# BHI_EVAL.net
KiCad netlist of a schematic drawn in Altium Designer
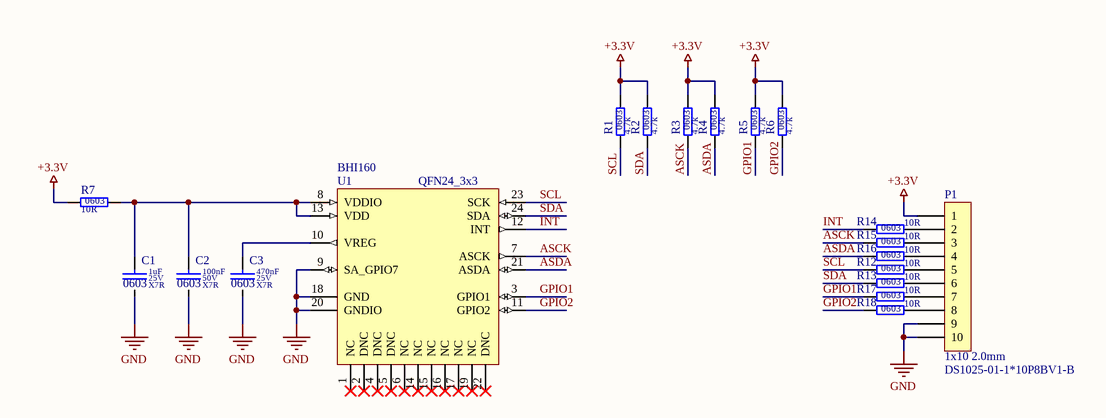
[diagram p0: BHI_EVAL.SchDoc]

(export (version "E")
  (design (tool "Eeschema 10.0.6"))
  (components
    (comp (ref "C1")
      (value "1uF")
      (footprint "C_0603_1608")
      (description "Capacitor")
      (fields
        (field (name "DIELECTRIC") "X7R")
        (field (name "VOLTAGE") "25V")
        (field (name "SCH_FOOTPRINT") "0603")
        (field (name "PART NUMBER") "C_1uF_25V_X7R_0603_10")
        (field (name "MANUFACTURER") "Samsung")
      )
      (libsource (lib "Library") (part "C"))
    )
    (comp (ref "C2")
      (value "100nF")
      (footprint "C_0603_1608")
      (description "Capacitor")
      (fields
        (field (name "DIELECTRIC") "X7R")
        (field (name "VOLTAGE") "50V")
        (field (name "SCH_FOOTPRINT") "0603")
        (field (name "PART NUMBER") "C_100nF_50V_X7R_0603_5")
        (field (name "MANUFACTURER") "Samsung")
      )
      (libsource (lib "Library") (part "C"))
    )
    (comp (ref "C3")
      (value "470nF")
      (footprint "C_0603_1608")
      (description "Capacitor")
      (fields
        (field (name "DIELECTRIC") "X7R")
        (field (name "VOLTAGE") "25V")
        (field (name "SCH_FOOTPRINT") "0603")
        (field (name "PART NUMBER") "C_470nF_25V_X7R_0603_10")
        (field (name "MANUFACTURER") "Murata")
      )
      (libsource (lib "Library") (part "C"))
    )
    (comp (ref "P1")
      (value "DS1025-01-1*10P8BV1-B")
      (footprint "P_HEADER_1x10_2.0")
      (description "Pin Header")
      (fields
        (field (name "SCH_FOOTPRINT") "1x10 2.0mm")
        (field (name "PART NUMBER") "P_HEADER_1x10_2.0")
        (field (name "MANUFACTURER") "Connfly")
      )
      (libsource (lib "Library") (part "P_HEADER_1x10"))
    )
    (comp (ref "R1")
      (value "4.7k")
      (footprint "R_0603_1608")
      (fields
        (field (name "SCH_FOOTPRINT") "0603")
        (field (name "PART NUMBER") "R_4.7k_0603_1")
        (field (name "VOLTAGE") "75V")
        (field (name "POWER") "100mW")
      )
      (libsource (lib "Library") (part "R"))
    )
    (comp (ref "R2")
      (value "4.7k")
      (footprint "R_0603_1608")
      (fields
        (field (name "SCH_FOOTPRINT") "0603")
        (field (name "PART NUMBER") "R_4.7k_0603_1")
        (field (name "VOLTAGE") "75V")
        (field (name "POWER") "100mW")
      )
      (libsource (lib "Library") (part "R"))
    )
    (comp (ref "R3")
      (value "4.7k")
      (footprint "R_0603_1608")
      (fields
        (field (name "SCH_FOOTPRINT") "0603")
        (field (name "PART NUMBER") "R_4.7k_0603_1")
        (field (name "VOLTAGE") "75V")
        (field (name "POWER") "100mW")
      )
      (libsource (lib "Library") (part "R"))
    )
    (comp (ref "R4")
      (value "4.7k")
      (footprint "R_0603_1608")
      (fields
        (field (name "SCH_FOOTPRINT") "0603")
        (field (name "PART NUMBER") "R_4.7k_0603_1")
        (field (name "VOLTAGE") "75V")
        (field (name "POWER") "100mW")
      )
      (libsource (lib "Library") (part "R"))
    )
    (comp (ref "R5")
      (value "4.7k")
      (footprint "R_0603_1608")
      (fields
        (field (name "SCH_FOOTPRINT") "0603")
        (field (name "PART NUMBER") "R_4.7k_0603_1")
        (field (name "VOLTAGE") "75V")
        (field (name "POWER") "100mW")
      )
      (libsource (lib "Library") (part "R"))
    )
    (comp (ref "R6")
      (value "4.7k")
      (footprint "R_0603_1608")
      (fields
        (field (name "SCH_FOOTPRINT") "0603")
        (field (name "PART NUMBER") "R_4.7k_0603_1")
        (field (name "VOLTAGE") "75V")
        (field (name "POWER") "100mW")
      )
      (libsource (lib "Library") (part "R"))
    )
    (comp (ref "R7")
      (value "10R")
      (footprint "R_0603_1608")
      (fields
        (field (name "SCH_FOOTPRINT") "0603")
        (field (name "PART NUMBER") "R_10R_0603_1")
        (field (name "VOLTAGE") "50V")
        (field (name "POWER") "100mW")
      )
      (libsource (lib "Library") (part "R"))
    )
    (comp (ref "R12")
      (value "10R")
      (footprint "R_0603_1608")
      (fields
        (field (name "SCH_FOOTPRINT") "0603")
        (field (name "PART NUMBER") "R_10R_0603_1")
        (field (name "VOLTAGE") "50V")
        (field (name "POWER") "100mW")
      )
      (libsource (lib "Library") (part "R"))
    )
    (comp (ref "R13")
      (value "10R")
      (footprint "R_0603_1608")
      (fields
        (field (name "SCH_FOOTPRINT") "0603")
        (field (name "PART NUMBER") "R_10R_0603_1")
        (field (name "VOLTAGE") "50V")
        (field (name "POWER") "100mW")
      )
      (libsource (lib "Library") (part "R"))
    )
    (comp (ref "R14")
      (value "10R")
      (footprint "R_0603_1608")
      (fields
        (field (name "SCH_FOOTPRINT") "0603")
        (field (name "PART NUMBER") "R_10R_0603_1")
        (field (name "VOLTAGE") "50V")
        (field (name "POWER") "100mW")
      )
      (libsource (lib "Library") (part "R"))
    )
    (comp (ref "R15")
      (value "10R")
      (footprint "R_0603_1608")
      (fields
        (field (name "SCH_FOOTPRINT") "0603")
        (field (name "PART NUMBER") "R_10R_0603_1")
        (field (name "VOLTAGE") "50V")
        (field (name "POWER") "100mW")
      )
      (libsource (lib "Library") (part "R"))
    )
    (comp (ref "R16")
      (value "10R")
      (footprint "R_0603_1608")
      (fields
        (field (name "SCH_FOOTPRINT") "0603")
        (field (name "PART NUMBER") "R_10R_0603_1")
        (field (name "VOLTAGE") "50V")
        (field (name "POWER") "100mW")
      )
      (libsource (lib "Library") (part "R"))
    )
    (comp (ref "R17")
      (value "10R")
      (footprint "R_0603_1608")
      (fields
        (field (name "SCH_FOOTPRINT") "0603")
        (field (name "PART NUMBER") "R_10R_0603_1")
        (field (name "VOLTAGE") "50V")
        (field (name "POWER") "100mW")
      )
      (libsource (lib "Library") (part "R"))
    )
    (comp (ref "R18")
      (value "10R")
      (footprint "R_0603_1608")
      (fields
        (field (name "SCH_FOOTPRINT") "0603")
        (field (name "PART NUMBER") "R_10R_0603_1")
        (field (name "VOLTAGE") "50V")
        (field (name "POWER") "100mW")
      )
      (libsource (lib "Library") (part "R"))
    )
    (comp (ref "U1")
      (value "BHI160")
      (footprint "QFN24_3x3")
      (fields
        (field (name "SCH_FOOTPRINT") "QFN24_3x3")
        (field (name "PART NUMBER") "U_BHI160")
        (field (name "MANUFACTURER") "Bosch Tools")
        (field (name "Comment") "Three Axis Ultra Low Power Sensor Hub - LGA-24")
      )
      (libsource (lib "Library") (part "U_BHI160"))
    )
  )
  (nets
    (net (code "1") (name "+3.3V") (class "Default")
      (node (ref "P1") (pin "1") (pinfunction "1_1") (pintype "passive"))
      (node (ref "R1") (pin "2") (pinfunction "2_2") (pintype "passive"))
      (node (ref "R2") (pin "2") (pinfunction "2_2") (pintype "passive"))
      (node (ref "R3") (pin "2") (pinfunction "2_2") (pintype "passive"))
      (node (ref "R4") (pin "2") (pinfunction "2_2") (pintype "passive"))
      (node (ref "R5") (pin "2") (pinfunction "2_2") (pintype "passive"))
      (node (ref "R6") (pin "2") (pinfunction "2_2") (pintype "passive"))
      (node (ref "R7") (pin "1") (pinfunction "1_1") (pintype "passive"))
    )
    (net (code "2") (name "/ASCK") (class "Default")
      (node (ref "R15") (pin "1") (pinfunction "1_1") (pintype "passive"))
      (node (ref "R3") (pin "1") (pinfunction "1_1") (pintype "passive"))
      (node (ref "U1") (pin "7") (pinfunction "ASCK_7") (pintype "output"))
    )
    (net (code "3") (name "/ASDA") (class "Default")
      (node (ref "R16") (pin "1") (pinfunction "1_1") (pintype "passive"))
      (node (ref "R4") (pin "1") (pinfunction "1_1") (pintype "passive"))
      (node (ref "U1") (pin "21") (pinfunction "ASDA_21") (pintype "bidirectional"))
    )
    (net (code "4") (name "/GPIO1") (class "Default")
      (node (ref "R17") (pin "1") (pinfunction "1_1") (pintype "passive"))
      (node (ref "R5") (pin "1") (pinfunction "1_1") (pintype "passive"))
      (node (ref "U1") (pin "3") (pinfunction "GPIO1_3") (pintype "bidirectional"))
    )
    (net (code "5") (name "/GPIO2") (class "Default")
      (node (ref "R18") (pin "1") (pinfunction "1_1") (pintype "passive"))
      (node (ref "R6") (pin "1") (pinfunction "1_1") (pintype "passive"))
      (node (ref "U1") (pin "11") (pinfunction "GPIO2_11") (pintype "bidirectional"))
    )
    (net (code "6") (name "/INT") (class "Default")
      (node (ref "R14") (pin "1") (pinfunction "1_1") (pintype "passive"))
      (node (ref "U1") (pin "12") (pinfunction "INT_12") (pintype "output"))
    )
    (net (code "7") (name "/SCL") (class "Default")
      (node (ref "R1") (pin "1") (pinfunction "1_1") (pintype "passive"))
      (node (ref "R12") (pin "1") (pinfunction "1_1") (pintype "passive"))
      (node (ref "U1") (pin "23") (pinfunction "SCK_23") (pintype "input"))
    )
    (net (code "8") (name "/SDA") (class "Default")
      (node (ref "R13") (pin "1") (pinfunction "1_1") (pintype "passive"))
      (node (ref "R2") (pin "1") (pinfunction "1_1") (pintype "passive"))
      (node (ref "U1") (pin "24") (pinfunction "SDA_24") (pintype "bidirectional"))
    )
    (net (code "9") (name "GND") (class "Default")
      (node (ref "C1") (pin "2") (pinfunction "2_2") (pintype "passive"))
      (node (ref "C2") (pin "2") (pinfunction "2_2") (pintype "passive"))
      (node (ref "C3") (pin "2") (pinfunction "2_2") (pintype "passive"))
      (node (ref "P1") (pin "10") (pinfunction "10_10") (pintype "passive"))
      (node (ref "P1") (pin "9") (pinfunction "9_9") (pintype "passive"))
      (node (ref "U1") (pin "18") (pinfunction "GND_18") (pintype "power_in"))
      (node (ref "U1") (pin "20") (pinfunction "GNDIO_20") (pintype "power_in"))
      (node (ref "U1") (pin "9") (pinfunction "SA_GPIO7_9") (pintype "bidirectional"))
    )
    (net (code "10") (name "Net-(P1-Pad2)") (class "Default")
      (node (ref "P1") (pin "2") (pinfunction "2_2") (pintype "passive"))
      (node (ref "R14") (pin "2") (pinfunction "2_2") (pintype "passive"))
    )
    (net (code "11") (name "Net-(P1-Pad3)") (class "Default")
      (node (ref "P1") (pin "3") (pinfunction "3_3") (pintype "passive"))
      (node (ref "R15") (pin "2") (pinfunction "2_2") (pintype "passive"))
    )
    (net (code "12") (name "Net-(P1-Pad4)") (class "Default")
      (node (ref "P1") (pin "4") (pinfunction "4_4") (pintype "passive"))
      (node (ref "R16") (pin "2") (pinfunction "2_2") (pintype "passive"))
    )
    (net (code "13") (name "Net-(P1-Pad5)") (class "Default")
      (node (ref "P1") (pin "5") (pinfunction "5_5") (pintype "passive"))
      (node (ref "R12") (pin "2") (pinfunction "2_2") (pintype "passive"))
    )
    (net (code "14") (name "Net-(P1-Pad6)") (class "Default")
      (node (ref "P1") (pin "6") (pinfunction "6_6") (pintype "passive"))
      (node (ref "R13") (pin "2") (pinfunction "2_2") (pintype "passive"))
    )
    (net (code "15") (name "Net-(P1-Pad7)") (class "Default")
      (node (ref "P1") (pin "7") (pinfunction "7_7") (pintype "passive"))
      (node (ref "R17") (pin "2") (pinfunction "2_2") (pintype "passive"))
    )
    (net (code "16") (name "Net-(P1-Pad8)") (class "Default")
      (node (ref "P1") (pin "8") (pinfunction "8_8") (pintype "passive"))
      (node (ref "R18") (pin "2") (pinfunction "2_2") (pintype "passive"))
    )
    (net (code "17") (name "Net-(U1-VDD)") (class "Default")
      (node (ref "C1") (pin "1") (pinfunction "1_1") (pintype "passive"))
      (node (ref "C2") (pin "1") (pinfunction "1_1") (pintype "passive"))
      (node (ref "R7") (pin "2") (pinfunction "2_2") (pintype "passive"))
      (node (ref "U1") (pin "13") (pinfunction "VDD_13") (pintype "input"))
      (node (ref "U1") (pin "8") (pinfunction "VDDIO_8") (pintype "input"))
    )
    (net (code "18") (name "Net-(U1-VREG)") (class "Default")
      (node (ref "C3") (pin "1") (pinfunction "1_1") (pintype "passive"))
      (node (ref "U1") (pin "10") (pinfunction "VREG_10") (pintype "output"))
    )
    (net (code "19") (name "unconnected-(U1-DNC-Pad2)") (class "Default")
      (node (ref "U1") (pin "2") (pinfunction "DNC_2") (pintype "passive+no_connect"))
    )
    (net (code "20") (name "unconnected-(U1-DNC-Pad4)") (class "Default")
      (node (ref "U1") (pin "4") (pinfunction "DNC_4") (pintype "passive+no_connect"))
    )
    (net (code "21") (name "unconnected-(U1-DNC-Pad5)") (class "Default")
      (node (ref "U1") (pin "5") (pinfunction "DNC_5") (pintype "passive+no_connect"))
    )
    (net (code "22") (name "unconnected-(U1-DNC-Pad22)") (class "Default")
      (node (ref "U1") (pin "22") (pinfunction "DNC_22") (pintype "passive+no_connect"))
    )
    (net (code "23") (name "unconnected-(U1-NC-Pad1)") (class "Default")
      (node (ref "U1") (pin "1") (pinfunction "NC_1") (pintype "passive+no_connect"))
    )
    (net (code "24") (name "unconnected-(U1-NC-Pad6)") (class "Default")
      (node (ref "U1") (pin "6") (pinfunction "NC_6") (pintype "passive+no_connect"))
    )
    (net (code "25") (name "unconnected-(U1-NC-Pad14)") (class "Default")
      (node (ref "U1") (pin "14") (pinfunction "NC_14") (pintype "passive+no_connect"))
    )
    (net (code "26") (name "unconnected-(U1-NC-Pad15)") (class "Default")
      (node (ref "U1") (pin "15") (pinfunction "NC_15") (pintype "passive+no_connect"))
    )
    (net (code "27") (name "unconnected-(U1-NC-Pad16)") (class "Default")
      (node (ref "U1") (pin "16") (pinfunction "NC_16") (pintype "passive+no_connect"))
    )
    (net (code "28") (name "unconnected-(U1-NC-Pad17)") (class "Default")
      (node (ref "U1") (pin "17") (pinfunction "NC_17") (pintype "passive+no_connect"))
    )
    (net (code "29") (name "unconnected-(U1-NC-Pad19)") (class "Default")
      (node (ref "U1") (pin "19") (pinfunction "NC_19") (pintype "passive+no_connect"))
    )
  )
)
